# Headphone-Amplifier-ClassAB-10x10.net
KiCad netlist of a schematic drawn in EAGLE
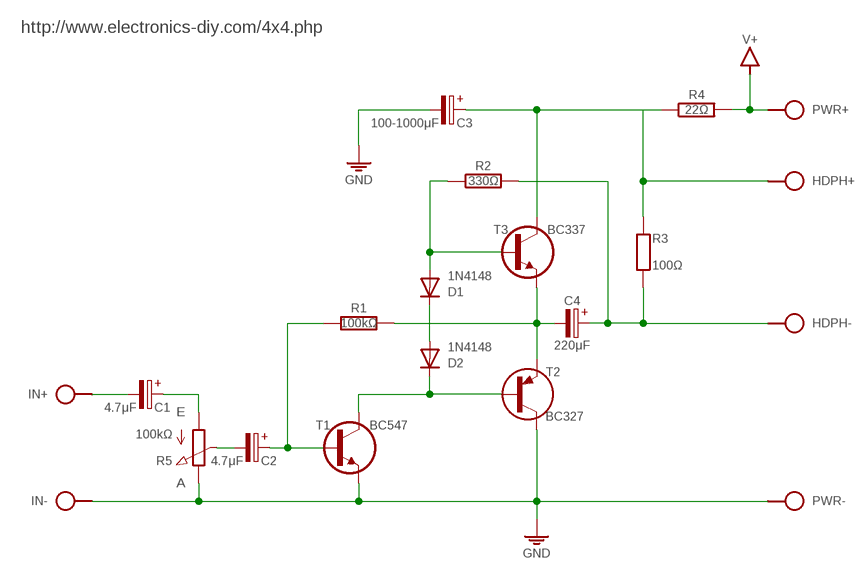
[diagram p0: schematic, sheet 1]

(export (version "E")
  (design (tool "Eeschema 10.0.6"))
  (components
    (comp (ref "C1")
      (value "4.7μF")
      (footprint "eagle-import:E2.5-4_V")
      (libsource (lib "eagle-import") (part "CPOL-HE2,5-4/V"))
    )
    (comp (ref "C2")
      (value "4.7μF")
      (footprint "eagle-import:E2.5-4_V")
      (libsource (lib "eagle-import") (part "CPOL-HE2,5-4/V"))
    )
    (comp (ref "C3")
      (value "100-1000μF")
      (footprint "eagle-import:E2,5-5_V")
      (libsource (lib "eagle-import") (part "CPOL-HE2,5-5/V"))
    )
    (comp (ref "C4")
      (value "220μF")
      (footprint "eagle-import:E5-6")
      (libsource (lib "eagle-import") (part "CPOLE5-6"))
    )
    (comp (ref "D1")
      (value "1N4148")
      (footprint "eagle-import:DO34-5")
      (libsource (lib "eagle-import") (part "1N414834-5"))
    )
    (comp (ref "D2")
      (value "1N4148")
      (footprint "eagle-import:DO34-5")
      (libsource (lib "eagle-import") (part "1N414834-5"))
    )
    (comp (ref "HDPH")
      (value "SPAD+--+")
      (footprint "eagle-import:SPAD-+")
      (libsource (lib "eagle-import") (part "SPAD+--+"))
    )
    (comp (ref "IN")
      (value "SPAD+-+-")
      (footprint "eagle-import:SPAD+-")
      (libsource (lib "eagle-import") (part "SPAD+-+-"))
    )
    (comp (ref "PWR")
      (value "SPAD+-+-")
      (footprint "eagle-import:SPAD+-")
      (libsource (lib "eagle-import") (part "SPAD+-+-"))
    )
    (comp (ref "R1")
      (value "100kΩ")
      (footprint "eagle-import:0202_7")
      (libsource (lib "eagle-import") (part "R-H0202/7"))
    )
    (comp (ref "R2")
      (value "330Ω")
      (footprint "eagle-import:0202_7")
      (libsource (lib "eagle-import") (part "R-H0202/7"))
    )
    (comp (ref "R3")
      (value "100Ω")
      (footprint "eagle-import:0202_7")
      (libsource (lib "eagle-import") (part "R0202/7"))
    )
    (comp (ref "R4")
      (value "22Ω")
      (footprint "eagle-import:0204_7")
      (libsource (lib "eagle-import") (part "R-H0204/7"))
    )
    (comp (ref "R5")
      (value "100kΩ")
      (footprint "eagle-import:CONN-3P")
      (libsource (lib "eagle-import") (part "POT-3P"))
    )
    (comp (ref "T1")
      (value "BC547")
      (footprint "eagle-import:TO92-CBE")
      (libsource (lib "eagle-import") (part "BC547CBE"))
    )
    (comp (ref "T2")
      (value "BC327")
      (footprint "eagle-import:TO92")
      (libsource (lib "eagle-import") (part "BC327"))
    )
    (comp (ref "T3")
      (value "BC337")
      (footprint "eagle-import:TO92-CBE")
      (libsource (lib "eagle-import") (part "BC337CBE"))
    )
  )
  (nets
    (net (code "1") (name "GND") (class "Default")
      (node (ref "C3") (pin "-") (pinfunction "-_-") (pintype "passive"))
      (node (ref "IN") (pin "1") (pinfunction "P$1_1") (pintype "passive"))
      (node (ref "PWR") (pin "1") (pinfunction "P$1_1") (pintype "passive"))
      (node (ref "R5") (pin "3") (pinfunction "E_3") (pintype "passive"))
      (node (ref "T1") (pin "E") (pinfunction "E_E") (pintype "passive"))
      (node (ref "T2") (pin "1") (pinfunction "C_1") (pintype "passive"))
    )
    (net (code "2") (name "Net-(C2-Pad+)") (class "Default")
      (node (ref "C2") (pin "+") (pinfunction "+_+") (pintype "passive"))
      (node (ref "R1") (pin "1") (pinfunction "1_1") (pintype "passive"))
      (node (ref "T1") (pin "B") (pinfunction "B_B") (pintype "passive"))
    )
    (net (code "3") (name "Net-(D1-PadA)") (class "Default")
      (node (ref "D1") (pin "A") (pinfunction "A_A") (pintype "passive"))
      (node (ref "R2") (pin "1") (pinfunction "1_1") (pintype "passive"))
      (node (ref "T3") (pin "B") (pinfunction "B_B") (pintype "passive"))
    )
    (net (code "4") (name "Net-(D1-PadC)") (class "Default")
      (node (ref "D1") (pin "C") (pinfunction "C_C") (pintype "passive"))
      (node (ref "D2") (pin "A") (pinfunction "A_A") (pintype "passive"))
    )
    (net (code "5") (name "Net-(HDPHA-P$1)") (class "Default")
      (node (ref "C3") (pin "+") (pinfunction "+_+") (pintype "passive"))
      (node (ref "HDPH") (pin "2") (pinfunction "P$1_2") (pintype "passive"))
      (node (ref "R3") (pin "1") (pinfunction "1_1") (pintype "passive"))
      (node (ref "R4") (pin "1") (pinfunction "1_1") (pintype "passive"))
      (node (ref "T3") (pin "C") (pinfunction "C_C") (pintype "passive"))
    )
    (net (code "6") (name "Net-(HDPHB-P$1)") (class "Default")
      (node (ref "C4") (pin "+") (pinfunction "+_+") (pintype "passive"))
      (node (ref "HDPH") (pin "1") (pinfunction "P$1_1") (pintype "passive"))
      (node (ref "R2") (pin "2") (pinfunction "2_2") (pintype "passive"))
      (node (ref "R3") (pin "2") (pinfunction "2_2") (pintype "passive"))
    )
    (net (code "7") (name "Net-(INA-P$1)") (class "Default")
      (node (ref "C1") (pin "-") (pinfunction "-_-") (pintype "passive"))
      (node (ref "IN") (pin "2") (pinfunction "P$1_2") (pintype "passive"))
    )
    (net (code "8") (name "Net-(R5-A)") (class "Default")
      (node (ref "C1") (pin "+") (pinfunction "+_+") (pintype "passive"))
      (node (ref "R5") (pin "1") (pinfunction "A_1") (pintype "passive"))
    )
    (net (code "9") (name "Net-(R5-S)") (class "Default")
      (node (ref "C2") (pin "-") (pinfunction "-_-") (pintype "passive"))
      (node (ref "R5") (pin "2") (pinfunction "S_2") (pintype "passive"))
    )
    (net (code "10") (name "Net-(T2-B)") (class "Default")
      (node (ref "D2") (pin "C") (pinfunction "C_C") (pintype "passive"))
      (node (ref "T1") (pin "C") (pinfunction "C_C") (pintype "passive"))
      (node (ref "T2") (pin "2") (pinfunction "B_2") (pintype "passive"))
    )
    (net (code "11") (name "Net-(T2-E)") (class "Default")
      (node (ref "C4") (pin "-") (pinfunction "-_-") (pintype "passive"))
      (node (ref "R1") (pin "2") (pinfunction "2_2") (pintype "passive"))
      (node (ref "T2") (pin "3") (pinfunction "E_3") (pintype "passive"))
      (node (ref "T3") (pin "E") (pinfunction "E_E") (pintype "passive"))
    )
    (net (code "12") (name "V+") (class "Default")
      (node (ref "PWR") (pin "2") (pinfunction "P$1_2") (pintype "passive"))
      (node (ref "R4") (pin "2") (pinfunction "2_2") (pintype "passive"))
    )
  )
)
